# Flash_Driver.net
KiCad netlist of a schematic drawn in Altium Designer
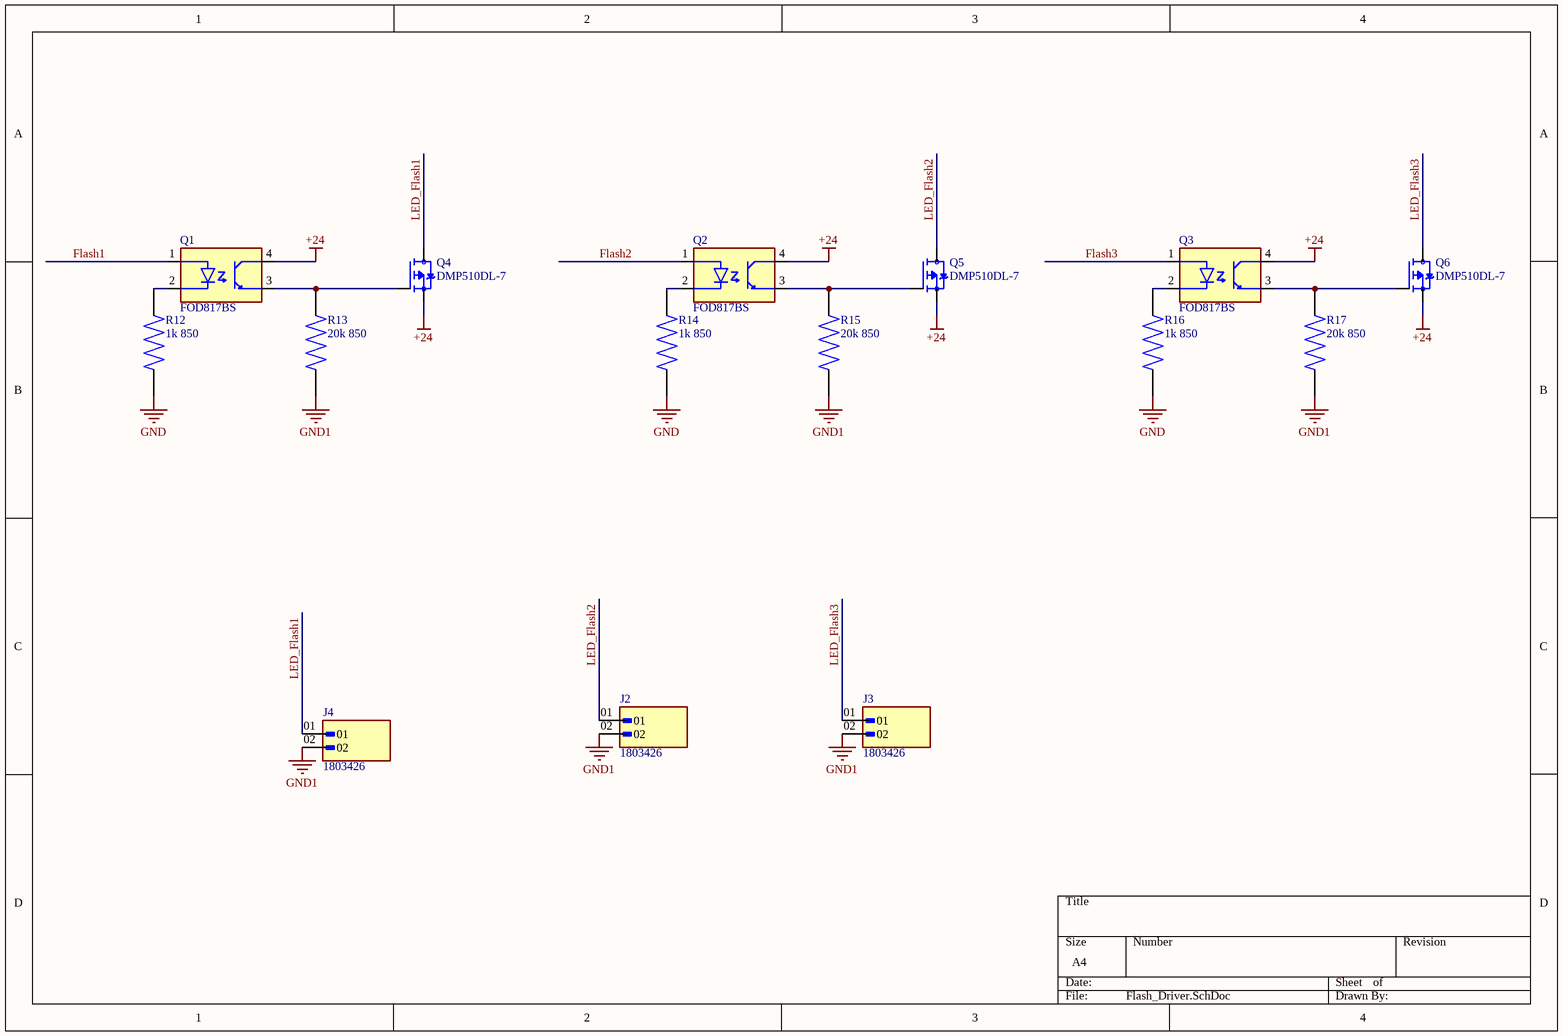
[diagram p0: Flash_Driver.SchDoc]

(export (version "E")
  (design (tool "Eeschema 10.0.6"))
  (components
    (comp (ref "J2")
      (value "1803426")
      (footprint "PHOENIX_1803426")
      (description "Pluggable Header 3.81mm 16AWG 160V 8A 2 Position COMBICON MCV Series ¦ Phoenix Contact 1803426")
      (fields (field (name "MF") "Phoenix Contact"))
      (libsource (lib "iee_altium") (part "1803426"))
    )
    (comp (ref "J3")
      (value "1803426")
      (footprint "PHOENIX_1803426")
      (description "Pluggable Header 3.81mm 16AWG 160V 8A 2 Position COMBICON MCV Series ¦ Phoenix Contact 1803426")
      (fields (field (name "MF") "Phoenix Contact"))
      (libsource (lib "iee_altium") (part "1803426"))
    )
    (comp (ref "J4")
      (value "1803426")
      (footprint "PHOENIX_1803426")
      (description "Pluggable Header 3.81mm 16AWG 160V 8A 2 Position COMBICON MCV Series ¦ Phoenix Contact 1803426")
      (fields (field (name "MF") "Phoenix Contact"))
      (libsource (lib "iee_altium") (part "1803426"))
    )
    (comp (ref "Q1")
      (value "FOD817BS")
      (footprint "SOIC254P1016X385-4N")
      (description "Transistor Output Optocouplers Opto Phototransistor Output SM-DIP4")
      (fields (field (name "MF") "ON Semiconductor"))
      (libsource (lib "iee_altium") (part "FOD817BS"))
    )
    (comp (ref "Q2")
      (value "FOD817BS")
      (footprint "SOIC254P1016X385-4N")
      (description "Transistor Output Optocouplers Opto Phototransistor Output SM-DIP4")
      (fields (field (name "MF") "ON Semiconductor"))
      (libsource (lib "iee_altium") (part "FOD817BS"))
    )
    (comp (ref "Q3")
      (value "FOD817BS")
      (footprint "SOIC254P1016X385-4N")
      (description "Transistor Output Optocouplers Opto Phototransistor Output SM-DIP4")
      (fields (field (name "MF") "ON Semiconductor"))
      (libsource (lib "iee_altium") (part "FOD817BS"))
    )
    (comp (ref "Q4")
      (value "DMP510DL-7")
      (footprint "SOT91P240X110-3N - duplicate")
      (libsource (lib "iee_altium") (part "DMP510DL-7"))
    )
    (comp (ref "Q5")
      (value "DMP510DL-7")
      (footprint "SOT91P240X110-3N - duplicate")
      (libsource (lib "iee_altium") (part "DMP510DL-7"))
    )
    (comp (ref "Q6")
      (value "DMP510DL-7")
      (footprint "SOT91P240X110-3N - duplicate")
      (libsource (lib "iee_altium") (part "DMP510DL-7"))
    )
    (comp (ref "R12") (value "1k 850") (footprint "10k 850") (libsource (lib "iee_altium") (part "10k 850")))
    (comp (ref "R13") (value "20k 850") (footprint "10k 850") (libsource (lib "iee_altium") (part "10k 850")))
    (comp (ref "R14") (value "1k 850") (footprint "10k 850") (libsource (lib "iee_altium") (part "10k 850")))
    (comp (ref "R15") (value "20k 850") (footprint "10k 850") (libsource (lib "iee_altium") (part "10k 850")))
    (comp (ref "R16") (value "1k 850") (footprint "10k 850") (libsource (lib "iee_altium") (part "10k 850")))
    (comp (ref "R17") (value "20k 850") (footprint "10k 850") (libsource (lib "iee_altium") (part "10k 850")))
  )
  (nets
    (net (code "1") (name "+24") (class "Default")
      (node (ref "Q1") (pin "4") (pinfunction "COLLECTOR_4") (pintype "passive"))
      (node (ref "Q2") (pin "4") (pinfunction "COLLECTOR_4") (pintype "passive"))
      (node (ref "Q3") (pin "4") (pinfunction "COLLECTOR_4") (pintype "passive"))
      (node (ref "Q4") (pin "2") (pinfunction "S_2") (pintype "passive"))
      (node (ref "Q5") (pin "2") (pinfunction "S_2") (pintype "passive"))
      (node (ref "Q6") (pin "2") (pinfunction "S_2") (pintype "passive"))
    )
    (net (code "2") (name "/Flash1") (class "Default")
      (node (ref "Q1") (pin "1") (pinfunction "ANODE_1") (pintype "passive"))
    )
    (net (code "3") (name "/Flash2") (class "Default")
      (node (ref "Q2") (pin "1") (pinfunction "ANODE_1") (pintype "passive"))
    )
    (net (code "4") (name "/Flash3") (class "Default")
      (node (ref "Q3") (pin "1") (pinfunction "ANODE_1") (pintype "passive"))
    )
    (net (code "5") (name "/LED_Flash1") (class "Default")
      (node (ref "J4") (pin "01") (pinfunction "01_01") (pintype "passive"))
      (node (ref "Q4") (pin "3") (pinfunction "D_3") (pintype "passive"))
    )
    (net (code "6") (name "/LED_Flash2") (class "Default")
      (node (ref "J2") (pin "01") (pinfunction "01_01") (pintype "passive"))
      (node (ref "Q5") (pin "3") (pinfunction "D_3") (pintype "passive"))
    )
    (net (code "7") (name "/LED_Flash3") (class "Default")
      (node (ref "J3") (pin "01") (pinfunction "01_01") (pintype "passive"))
      (node (ref "Q6") (pin "3") (pinfunction "D_3") (pintype "passive"))
    )
    (net (code "8") (name "GND") (class "Default")
      (node (ref "R12") (pin "2") (pinfunction "2_2") (pintype "passive"))
      (node (ref "R14") (pin "2") (pinfunction "2_2") (pintype "passive"))
      (node (ref "R16") (pin "2") (pinfunction "2_2") (pintype "passive"))
    )
    (net (code "9") (name "GND1") (class "Default")
      (node (ref "J2") (pin "02") (pinfunction "02_02") (pintype "passive"))
      (node (ref "J3") (pin "02") (pinfunction "02_02") (pintype "passive"))
      (node (ref "J4") (pin "02") (pinfunction "02_02") (pintype "passive"))
      (node (ref "R13") (pin "2") (pinfunction "2_2") (pintype "passive"))
      (node (ref "R15") (pin "2") (pinfunction "2_2") (pintype "passive"))
      (node (ref "R17") (pin "2") (pinfunction "2_2") (pintype "passive"))
    )
    (net (code "10") (name "Net-(Q1-CATHODE)") (class "Default")
      (node (ref "Q1") (pin "2") (pinfunction "CATHODE_2") (pintype "passive"))
      (node (ref "R12") (pin "1") (pinfunction "1_1") (pintype "passive"))
    )
    (net (code "11") (name "Net-(Q1-EMITTER)") (class "Default")
      (node (ref "Q1") (pin "3") (pinfunction "EMITTER_3") (pintype "passive"))
      (node (ref "Q4") (pin "1") (pinfunction "G_1") (pintype "passive"))
      (node (ref "R13") (pin "1") (pinfunction "1_1") (pintype "passive"))
    )
    (net (code "12") (name "Net-(Q2-CATHODE)") (class "Default")
      (node (ref "Q2") (pin "2") (pinfunction "CATHODE_2") (pintype "passive"))
      (node (ref "R14") (pin "1") (pinfunction "1_1") (pintype "passive"))
    )
    (net (code "13") (name "Net-(Q2-EMITTER)") (class "Default")
      (node (ref "Q2") (pin "3") (pinfunction "EMITTER_3") (pintype "passive"))
      (node (ref "Q5") (pin "1") (pinfunction "G_1") (pintype "passive"))
      (node (ref "R15") (pin "1") (pinfunction "1_1") (pintype "passive"))
    )
    (net (code "14") (name "Net-(Q3-CATHODE)") (class "Default")
      (node (ref "Q3") (pin "2") (pinfunction "CATHODE_2") (pintype "passive"))
      (node (ref "R16") (pin "1") (pinfunction "1_1") (pintype "passive"))
    )
    (net (code "15") (name "Net-(Q3-EMITTER)") (class "Default")
      (node (ref "Q3") (pin "3") (pinfunction "EMITTER_3") (pintype "passive"))
      (node (ref "Q6") (pin "1") (pinfunction "G_1") (pintype "passive"))
      (node (ref "R17") (pin "1") (pinfunction "1_1") (pintype "passive"))
    )
  )
)
